# Connector_Sheet.net
KiCad netlist of a schematic drawn in Altium Designer
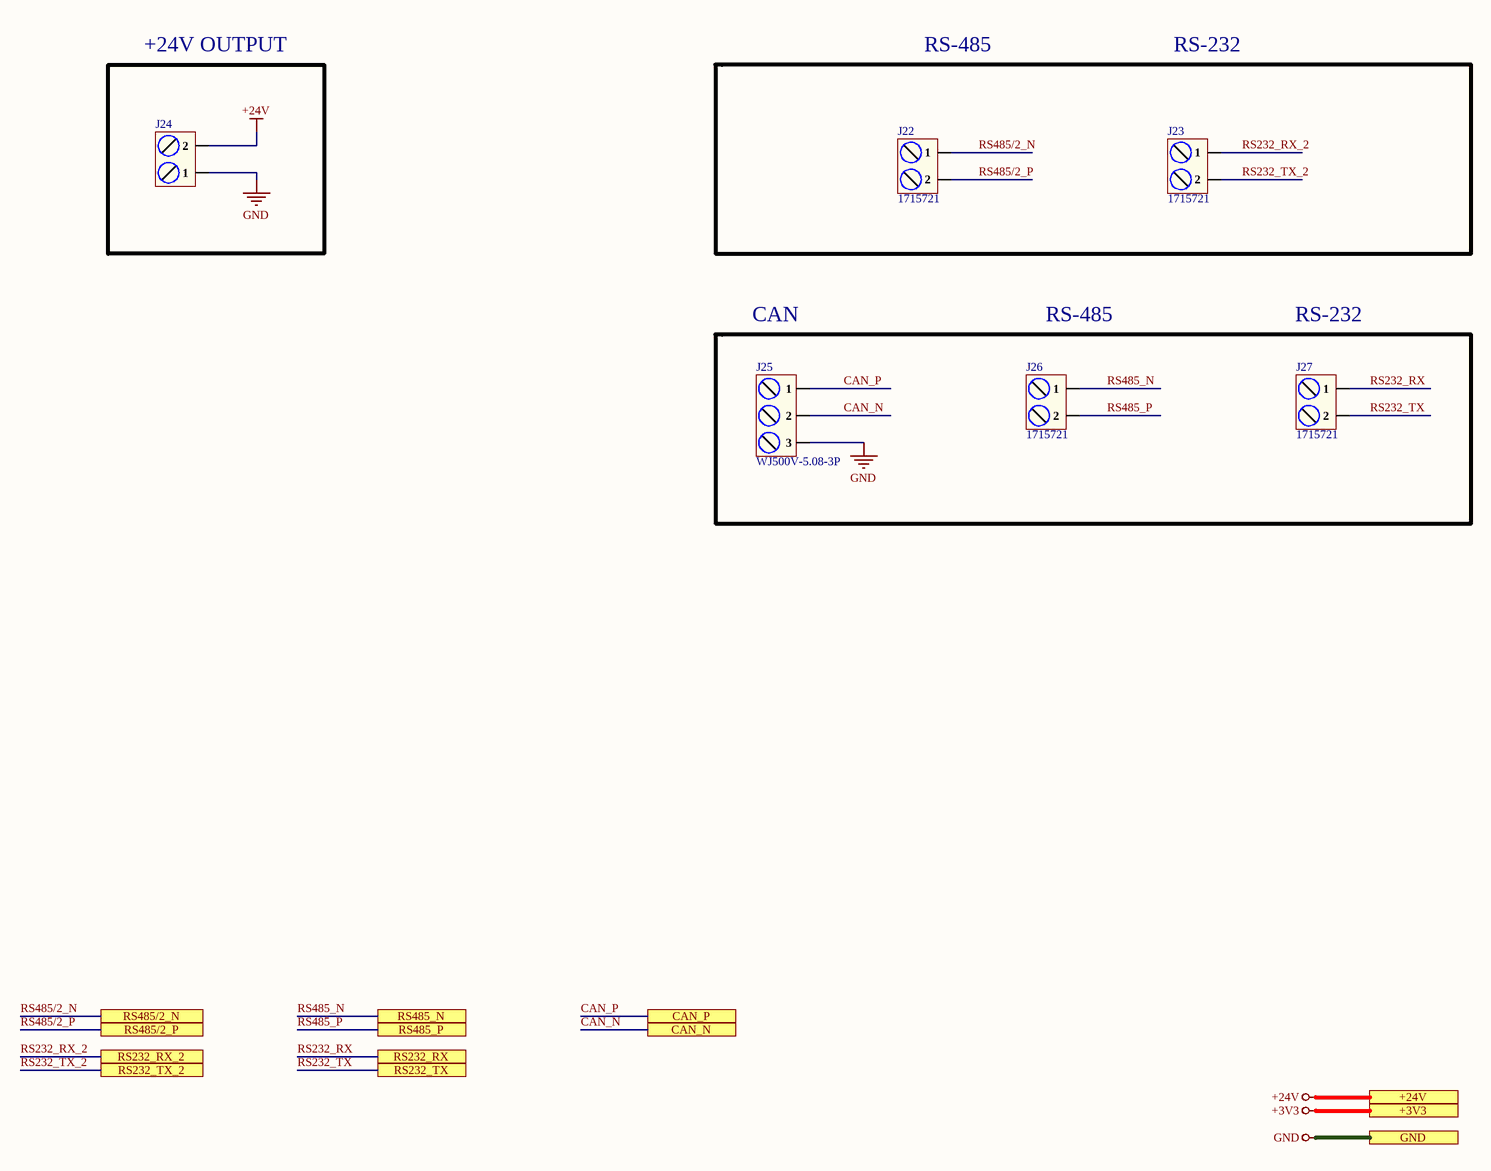
[diagram p0: Connector_Sheet.SchDoc]

(export (version "E")
  (design (tool "Eeschema 10.0.6"))
  (components
    (comp (ref "J22")
      (value "1715721")
      (footprint "1715721")
      (description "TERM BLK 2P SIDE ENT 5.08MM PCB")
      (fields (field (name "MANUFACTURER") "Phoenix Contact"))
      (libsource (lib "eSpark Libraries") (part "1715721"))
    )
    (comp (ref "J23")
      (value "1715721")
      (footprint "1715721")
      (description "TERM BLK 2P SIDE ENT 5.08MM PCB")
      (fields (field (name "MANUFACTURER") "Phoenix Contact"))
      (libsource (lib "eSpark Libraries") (part "1715721"))
    )
    (comp (ref "J24")
      (value "MXHB9500-9.5-02P-BK01-Cu-S-A")
      (footprint "MXHB9500-9.5-02P-BK01-Cu-S-A")
      (fields (field (name "MANUFACTURER") "MAX") (field (name "LCSC PART NUMBER") "C7542168"))
      (libsource (lib "eSpark Libraries") (part "MXHB9500-9.5-02P-BK01-Cu-S-A"))
    )
    (comp (ref "J25")
      (value "WJ500V-5.08-3P")
      (footprint "WJ500V-5.08-3P")
      (fields (field (name "MANUFACTURER") "Ningbo Kangnex Elec") (field (name "LCSC PART NUMBER") "C72334"))
      (libsource (lib "eSpark Libraries") (part "WJ500V-5.08-3P"))
    )
    (comp (ref "J26")
      (value "1715721")
      (footprint "1715721")
      (description "TERM BLK 2P SIDE ENT 5.08MM PCB")
      (fields (field (name "MANUFACTURER") "Phoenix Contact"))
      (libsource (lib "eSpark Libraries") (part "1715721"))
    )
    (comp (ref "J27")
      (value "1715721")
      (footprint "1715721")
      (description "TERM BLK 2P SIDE ENT 5.08MM PCB")
      (fields (field (name "MANUFACTURER") "Phoenix Contact"))
      (libsource (lib "eSpark Libraries") (part "1715721"))
    )
  )
  (nets
    (net (code "2") (name "+24V") (class "Default")
      (node (ref "J24") (pin "2") (pinfunction "2_2") (pintype "passive"))
    )
    (net (code "3") (name "/CAN_N") (class "Default")
      (node (ref "J25") (pin "2") (pinfunction "2_2") (pintype "passive"))
    )
    (net (code "4") (name "/CAN_P") (class "Default")
      (node (ref "J25") (pin "1") (pinfunction "1_1") (pintype "passive"))
    )
    (net (code "5") (name "/RS232_RX") (class "Default")
      (node (ref "J27") (pin "1") (pinfunction "1_1") (pintype "passive"))
    )
    (net (code "6") (name "/RS232_RX_2") (class "Default")
      (node (ref "J23") (pin "1") (pinfunction "1_1") (pintype "passive"))
    )
    (net (code "7") (name "/RS232_TX") (class "Default")
      (node (ref "J27") (pin "2") (pinfunction "2_2") (pintype "passive"))
    )
    (net (code "8") (name "/RS232_TX_2") (class "Default")
      (node (ref "J23") (pin "2") (pinfunction "2_2") (pintype "passive"))
    )
    (net (code "9") (name "/RS485_N") (class "Default")
      (node (ref "J26") (pin "1") (pinfunction "1_1") (pintype "passive"))
    )
    (net (code "10") (name "/RS485_P") (class "Default")
      (node (ref "J26") (pin "2") (pinfunction "2_2") (pintype "passive"))
    )
    (net (code "11") (name "/RS485{slash}2_N") (class "Default")
      (node (ref "J22") (pin "1") (pinfunction "1_1") (pintype "passive"))
    )
    (net (code "12") (name "/RS485{slash}2_P") (class "Default")
      (node (ref "J22") (pin "2") (pinfunction "2_2") (pintype "passive"))
    )
    (net (code "13") (name "GND") (class "Default")
      (node (ref "J24") (pin "1") (pinfunction "1_1") (pintype "passive"))
      (node (ref "J25") (pin "3") (pinfunction "3_3") (pintype "passive"))
    )
  )
)
